# 24_to_33V__for_Ionizer_Chips.net
KiCad netlist of a schematic drawn in Altium Designer
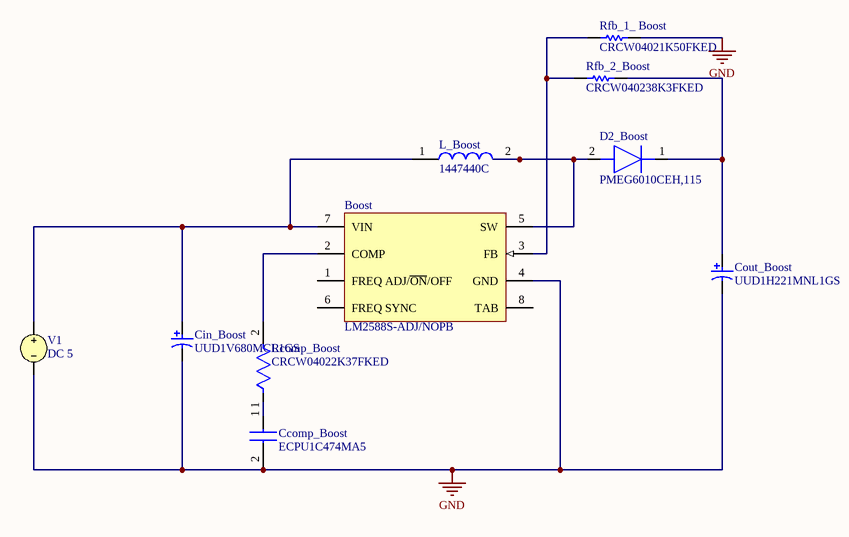
[diagram p0: 24_to_33V_(for_Ionizer_Chips).SchDoc]

(export (version "E")
  (design (tool "Eeschema 10.0.6"))
  (components
    (comp (ref "Boost")
      (value "LM2588S-ADJ/NOPB")
      (footprint "KTW0007B_N")
      (description "SIMPLE SWITCHER® 5A Flyback Regulator with Shutdown, 7-pin TO-263, Pb-Free")
      (fields (field (name "MANUFACTURER") "Texas Instruments"))
      (libsource (lib "Altium Content Vault") (part "PM-SWREG-LM2586S-12"))
    )
    (comp (ref "Ccomp_Boost")
      (value "ECPU1C474MA5")
      (footprint "SamacSys:ECPU1C154MA5")
      (description "Capacitor")
      (libsource (lib "*") (part "ECPU1C474MA5"))
    )
    (comp (ref "Cin_Boost")
      (value "UUD1V680MCL1GS")
      (footprint "NIC-CAPA2-6.3X7.7_V")
      (fields (field (name "MANUFACTURER") "Nichicon"))
      (libsource (lib "Altium Content Vault") (part "NIC-CAP-P-2"))
    )
    (comp (ref "Cout_Boost")
      (value "UUD1H221MNL1GS")
      (footprint "NIC-CAPA2-10X10_V")
      (fields (field (name "MANUFACTURER") "Nichicon"))
      (libsource (lib "Altium Content Vault") (part "NIC-CAP-P-2"))
    )
    (comp (ref "D2_Boost")
      (value "PMEG6010CEH,115")
      (footprint "SamacSys:SODFL3516X120N")
      (description "Diode")
      (fields (field (name "MOUSER PART NUMBER") "771-PMEG6010CEH-T/R"))
      (libsource (lib "*") (part "PMEG6010CEH,115"))
    )
    (comp (ref "L_Boost")
      (value "1447440C")
      (footprint "SamacSys:1447440C")
      (description "Inductor")
      (fields (field (name "MOUSER PART NUMBER") "580-1447440C"))
      (libsource (lib "*") (part "1447440C"))
    )
    (comp (ref "Rcomp_Boost")
      (value "CRCW04022K37FKED")
      (footprint "FP-CRCW0402-e3-IPC_B")
      (description "RES Thick Film, 2.37kΩ, 1%, 0.063W, 100ppm/°C, 0402")
      (fields (field (name "TOLERANCE") "1%"))
      (libsource (lib "Altium Content Vault") (part "1029c3af85768c4190bb7ad29bc67b5"))
    )
    (comp (ref "Rfb_1_ Boost")
      (value "CRCW04021K50FKED")
      (footprint "RESC1005X40X25NL05T05")
      (fields (field (name "MANUFACTURER") "Vishay Dale"))
      (libsource (lib "Altium Content Vault") (part "RES"))
    )
    (comp (ref "Rfb_2_Boost")
      (value "CRCW040238K3FKED")
      (footprint "RESC1005X40X25NL05T05")
      (fields (field (name "MANUFACTURER") "Vishay Dale"))
      (libsource (lib "Altium Content Vault") (part "RES"))
    )
    (comp (ref "V1")
      (value "DC 5")
      (description "Voltage Source")
      (fields (field (name "PUBLISHER") "Altium Limited"))
      (libsource (lib "Simulation Generic Components") (part "VSRC"))
    )
  )
  (nets
    (net (code "1") (name "GND") (class "Default")
      (node (ref "Boost") (pin "4") (pinfunction "GND_4") (pintype "power_in"))
      (node (ref "Ccomp_Boost") (pin "2") (pinfunction "2_2") (pintype "passive"))
      (node (ref "Cin_Boost") (pin "2") (pinfunction "2_2") (pintype "passive"))
      (node (ref "Cout_Boost") (pin "2") (pinfunction "2_2") (pintype "passive"))
      (node (ref "Rfb_1_ Boost") (pin "2") (pinfunction "2_2") (pintype "passive"))
      (node (ref "V1") (pin "2") (pinfunction "2_2") (pintype "passive"))
    )
    (net (code "2") (name "Net-(Boost-COMP)") (class "Default")
      (node (ref "Boost") (pin "2") (pinfunction "COMP_2") (pintype "passive"))
      (node (ref "Rcomp_Boost") (pin "2") (pinfunction "2_2") (pintype "passive"))
    )
    (net (code "3") (name "Net-(Boost-FB)") (class "Default")
      (node (ref "Boost") (pin "3") (pinfunction "FB_3") (pintype "input"))
      (node (ref "Rfb_1_ Boost") (pin "1") (pinfunction "1_1") (pintype "passive"))
      (node (ref "Rfb_2_Boost") (pin "1") (pinfunction "1_1") (pintype "passive"))
    )
    (net (code "4") (name "Net-(Boost-SW)") (class "Default")
      (node (ref "Boost") (pin "5") (pinfunction "SW_5") (pintype "power_in"))
      (node (ref "D2_Boost") (pin "2") (pinfunction "A_2") (pintype "passive"))
      (node (ref "L_Boost") (pin "2") (pinfunction "2_2") (pintype "passive"))
    )
    (net (code "5") (name "Net-(Boost-VIN)") (class "Default")
      (node (ref "Boost") (pin "7") (pinfunction "VIN_7") (pintype "power_in"))
      (node (ref "Cin_Boost") (pin "1") (pinfunction "1_1") (pintype "passive"))
      (node (ref "L_Boost") (pin "1") (pinfunction "1_1") (pintype "passive"))
      (node (ref "V1") (pin "1") (pinfunction "1_1") (pintype "passive"))
    )
    (net (code "6") (name "Net-(Ccomp_Boost-Pad1)") (class "Default")
      (node (ref "Ccomp_Boost") (pin "1") (pinfunction "1_1") (pintype "passive"))
      (node (ref "Rcomp_Boost") (pin "1") (pinfunction "1_1") (pintype "passive"))
    )
    (net (code "7") (name "Net-(D2_Boost-K)") (class "Default")
      (node (ref "Cout_Boost") (pin "1") (pinfunction "1_1") (pintype "passive"))
      (node (ref "D2_Boost") (pin "1") (pinfunction "K_1") (pintype "passive"))
      (node (ref "Rfb_2_Boost") (pin "2") (pinfunction "2_2") (pintype "passive"))
    )
    (net (code "8") (name "unconnected-(Boost-FREQ_ADJ{slash}~{ON}{slash}OFF-Pad1)") (class "Default")
      (node (ref "Boost") (pin "1") (pinfunction "FREQ_ADJ/~{ON}/OFF_1") (pintype "passive"))
    )
    (net (code "9") (name "unconnected-(Boost-FREQ_SYNC-Pad6)") (class "Default")
      (node (ref "Boost") (pin "6") (pinfunction "FREQ_SYNC_6") (pintype "passive"))
    )
    (net (code "10") (name "unconnected-(Boost-TAB-Pad8)") (class "Default")
      (node (ref "Boost") (pin "8") (pinfunction "TAB_8") (pintype "passive"))
    )
  )
)
